# power-v1v35.net
KiCad netlist of a schematic drawn in Altium Designer
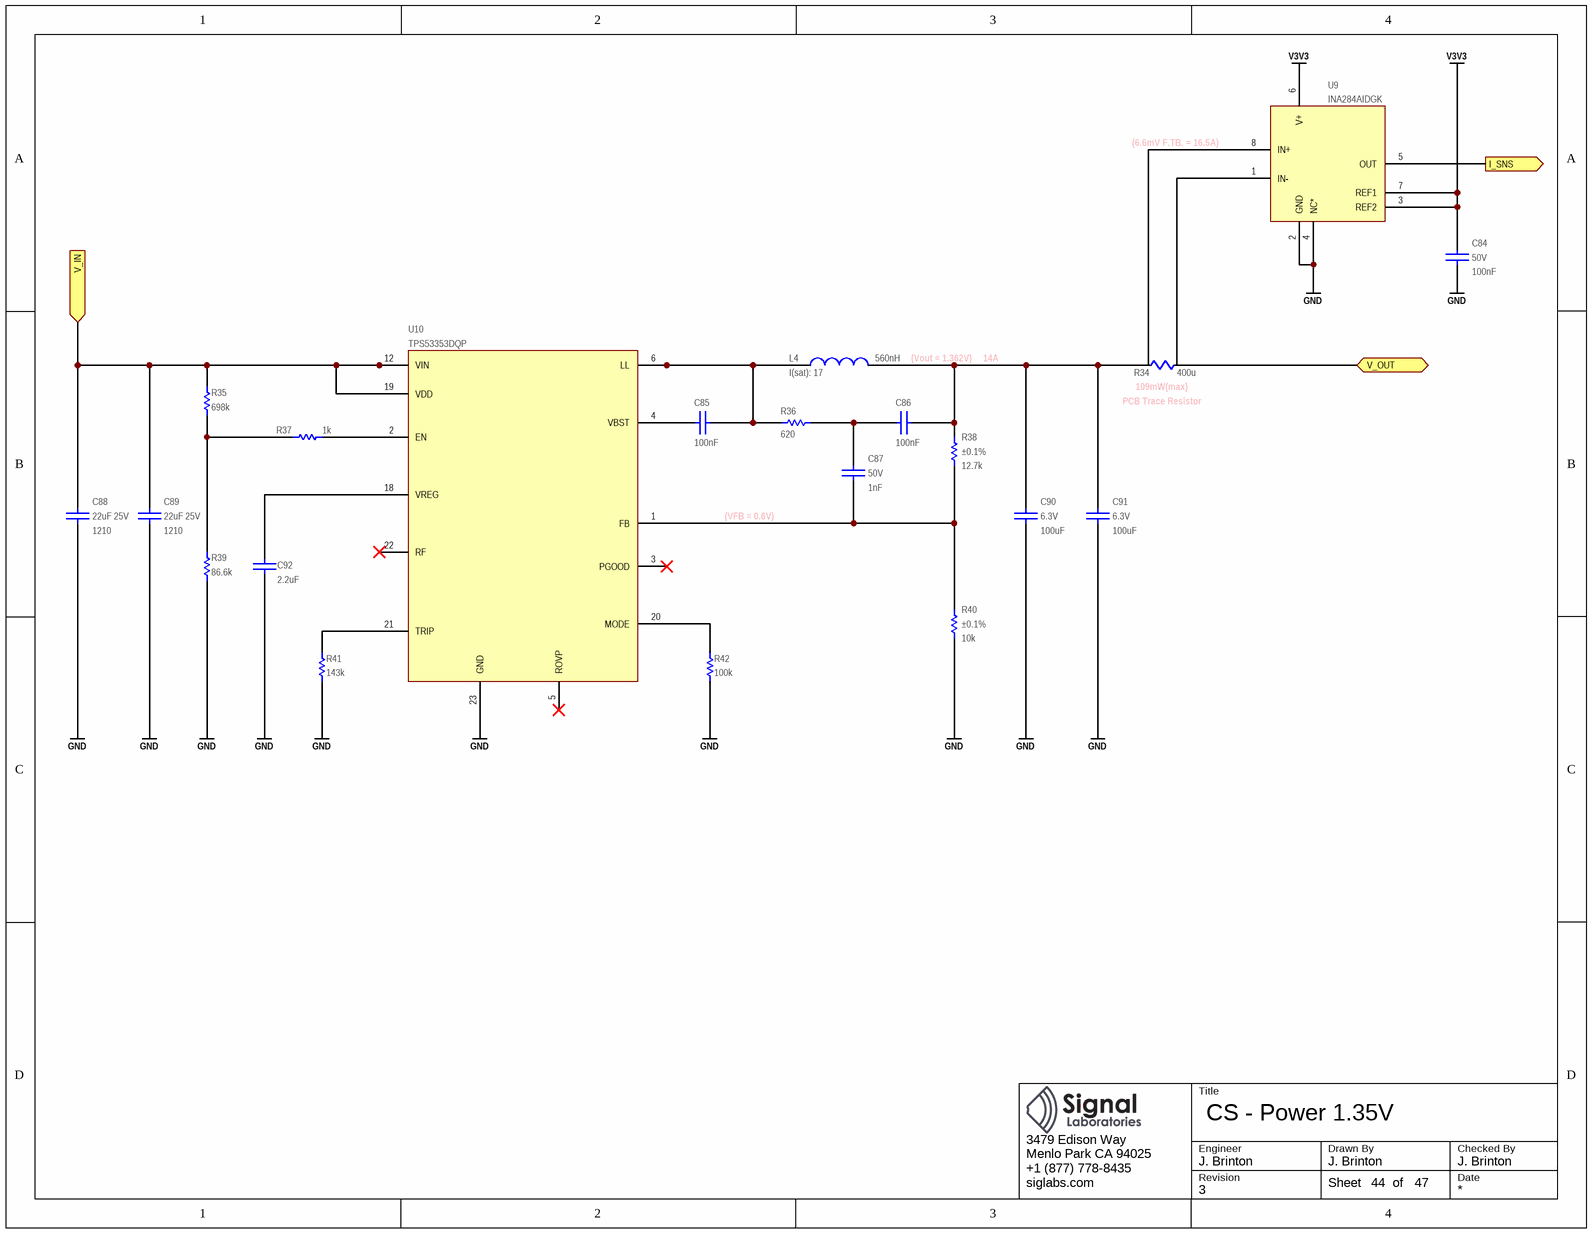
[diagram p0: power-v1v35.SchDoc]

(export (version "E")
  (design (tool "Eeschema 10.0.6"))
  (components
    (comp (ref "C84")
      (value "100nF")
      (footprint "CAPC100X50X55L25N")
      (description "Ceramic Capacitor 100nF ±10% 50V X7R 0402")
      (fields
        (field (name "MANUFACTURER") "Murata")
        (field (name "TOLERANCE") "±10%")
        (field (name "VOLTAGE") "50V")
      )
      (libsource (lib "") (part "CAP_1"))
    )
    (comp (ref "C85")
      (value "100nF")
      (footprint "CAPC100X50X55L25N")
      (description "Ceramic Capacitor 100nF ±10% 50V X7R 0402")
      (fields (field (name "MANUFACTURER") "Murata") (field (name "VOLTAGE") "50V"))
      (libsource (lib "generic") (part "CAP"))
    )
    (comp (ref "C86")
      (value "100nF")
      (footprint "CAPC100X50X55L25N")
      (description "Ceramic Capacitor 100nF ±10% 50V X7R 0402")
      (fields (field (name "MANUFACTURER") "Murata") (field (name "VOLTAGE") "50V"))
      (libsource (lib "generic") (part "CAP"))
    )
    (comp (ref "C87")
      (value "1nF")
      (footprint "CAPC100X50X55L25N")
      (description "Ceramic Capacitor 1nF ±10% 50V X7R 0402")
      (fields
        (field (name "MANUFACTURER") "Murata")
        (field (name "TOLERANCE") "±10%")
        (field (name "VOLTAGE") "50V")
      )
      (libsource (lib "") (part "CAP_1"))
    )
    (comp (ref "C88")
      (value "22uF")
      (footprint "CAPC320X250X270L50N")
      (description "Ceramic Capacitor 22uF ±10% 25V X7R 1210")
      (fields
        (field (name "MANUFACTURER") "Murata")
        (field (name "TOLERANCE") "±10%")
        (field (name "VOLTAGE") "25V")
        (field (name "PACKAGE") "1210")
      )
      (libsource (lib "generic") (part "CAP"))
    )
    (comp (ref "C89")
      (value "22uF")
      (footprint "CAPC320X250X270L50N")
      (description "Ceramic Capacitor 22uF ±10% 25V X7R 1210")
      (fields
        (field (name "MANUFACTURER") "Murata")
        (field (name "TOLERANCE") "±10%")
        (field (name "VOLTAGE") "25V")
        (field (name "PACKAGE") "1210")
      )
      (libsource (lib "generic") (part "CAP"))
    )
    (comp (ref "C90")
      (value "100uF")
      (footprint "CAPC320X250X280L50N")
      (description "Ceramic Capacitor 100uF ±20% 6.3V X6S 1210")
      (fields
        (field (name "MANUFACTURER") "TDK")
        (field (name "TOLERANCE") "±20%")
        (field (name "VOLTAGE") "6.3V")
      )
      (libsource (lib "") (part "CAP_1"))
    )
    (comp (ref "C91")
      (value "100uF")
      (footprint "CAPC320X250X280L50N")
      (description "Ceramic Capacitor 100uF ±20% 6.3V X6S 1210")
      (fields
        (field (name "MANUFACTURER") "TDK")
        (field (name "TOLERANCE") "±20%")
        (field (name "VOLTAGE") "6.3V")
      )
      (libsource (lib "") (part "CAP_1"))
    )
    (comp (ref "C92")
      (value "2.2uF")
      (footprint "CAPC160X80X90L20N")
      (description "Ceramic Capacitor 2.2uF ±20% 10V X7R 0603")
      (fields (field (name "MANUFACTURER") "TDK") (field (name "TOLERANCE") "±20%"))
      (libsource (lib "generic") (part "CAP"))
    )
    (comp (ref "L4")
      (value "560nH")
      (footprint "coilcraft:XAL6030")
      (description "Shielded Power Inductor 560nH, 17A")
      (fields
        (field (name "MANUFACTURER") "Coilcraft")
        (field (name "I(SAT)") "17")
        (field (name "Comment") "XAL6030-561ME")
      )
      (libsource (lib "generic") (part "INDUCTOR"))
    )
    (comp (ref "R34")
      (value "400u")
      (footprint "RES0.0004")
      (description "Current Sense Resistor 400uOhm TRACE")
      (fields (field (name "Comment") "RES0.0004"))
      (libsource (lib "copper_suicide") (part "RES0.0004"))
    )
    (comp (ref "R35")
      (value "698k")
      (footprint "RESC1005X40N")
      (description "Thick Film Resistor 698k ±1% 0.1W 50V 0402")
      (fields (field (name "MANUFACTURER") "Panasonic") (field (name "TOLERANCE") "±1%"))
      (libsource (lib "generic") (part "RES"))
    )
    (comp (ref "R36")
      (value "620")
      (footprint "RESC1005X40N")
      (description "Thick Film Resistor 620 ±1% 0.1W 50V 0402")
      (fields (field (name "MANUFACTURER") "Panasonic") (field (name "TOLERANCE") "±1%"))
      (libsource (lib "generic") (part "RES"))
    )
    (comp (ref "R37")
      (value "1k")
      (footprint "RESC1005X40N")
      (description "Thick Film Resistor 1k ±1% 0.1W 50V 0402")
      (fields (field (name "MANUFACTURER") "Panasonic") (field (name "TOLERANCE") "±1%"))
      (libsource (lib "generic") (part "RES"))
    )
    (comp (ref "R38")
      (value "12.7k")
      (footprint "RESC2012X70N")
      (description "Thin Film Resistor 12.7k ±0.1% 0.125W 100V 0805")
      (fields
        (field (name "TOLERANCE") "±0.1%")
        (field (name "MANUFACTURER") "Panasonic")
        (field (name "VOLTAGE") "100")
      )
      (libsource (lib "generic") (part "RES"))
    )
    (comp (ref "R39")
      (value "86.6k")
      (footprint "RESC1005X40N")
      (description "Thick Film Resistor 86.6k ±1% 0.1W 50V 0402")
      (fields (field (name "MANUFACTURER") "Panasonic") (field (name "TOLERANCE") "±1%"))
      (libsource (lib "generic") (part "RES"))
    )
    (comp (ref "R40")
      (value "10k")
      (footprint "RESC2012X70N")
      (description "Thin Film Resistor 10k ±0.1% 0.125W 100V 0805")
      (fields
        (field (name "TOLERANCE") "±0.1%")
        (field (name "MANUFACTURER") "Panasonic")
        (field (name "VOLTAGE") "100")
      )
      (libsource (lib "generic") (part "RES"))
    )
    (comp (ref "R41")
      (value "143k")
      (footprint "RESC1005X40N")
      (description "Thick Film Resistor 143k ±1% 0.1W 50V 0402")
      (fields (field (name "MANUFACTURER") "Panasonic") (field (name "TOLERANCE") "±1%"))
      (libsource (lib "generic") (part "RES"))
    )
    (comp (ref "R42")
      (value "100k")
      (footprint "RESC1005X40N")
      (description "Thick Film Resistor 100k ±1% 0.1W 50V 0402")
      (fields (field (name "MANUFACTURER") "Panasonic") (field (name "TOLERANCE") "±1%"))
      (libsource (lib "generic") (part "RES"))
    )
    (comp (ref "U9")
      (value "INA284AIDGK")
      (footprint "texas_instruments:S-PDSO-G8")
      (description "Bidirectional Current Shunt Monitor")
      (fields (field (name "MANUFACTURER") "Texas Instruments"))
      (libsource (lib "ti") (part "INA283AIDGK"))
    )
    (comp (ref "U10")
      (value "TPS53353DQP")
      (footprint "texas_instruments:DQP")
      (description "Synchronous Buck Converter 20A")
      (fields
        (field (name "MANUFACTURER") "Texas Instruments")
        (field (name "MANUFACTURER P/N") "TPS53353DQP")
      )
      (libsource (lib "ti") (part "TPS53319DQPR"))
    )
  )
  (nets
    (net (code "1") (name "/I_SNS") (class "Default")
      (node (ref "U9") (pin "5") (pinfunction "OUT_5") (pintype "passive"))
    )
    (net (code "2") (name "/V_IN") (class "Default")
      (node (ref "C88") (pin "2") (pinfunction "2_2") (pintype "passive"))
      (node (ref "C89") (pin "2") (pinfunction "2_2") (pintype "passive"))
      (node (ref "R35") (pin "1") (pinfunction "1_1") (pintype "passive"))
      (node (ref "U10") (pin "12") (pinfunction "VIN_12") (pintype "passive"))
      (node (ref "U10") (pin "13") (pinfunction "VIN_13") (pintype "passive"))
      (node (ref "U10") (pin "14") (pinfunction "VIN_14") (pintype "passive"))
      (node (ref "U10") (pin "15") (pinfunction "VIN_15") (pintype "passive"))
      (node (ref "U10") (pin "16") (pinfunction "VIN_16") (pintype "passive"))
      (node (ref "U10") (pin "17") (pinfunction "VIN_17") (pintype "passive"))
      (node (ref "U10") (pin "19") (pinfunction "VDD_19") (pintype "passive"))
    )
    (net (code "3") (name "/V_OUT") (class "Default") (node (ref "R34") (pin "2") (pintype "passive")))
    (net (code "4") (name "GND") (class "Default")
      (node (ref "C84") (pin "1") (pinfunction "1_1") (pintype "passive"))
      (node (ref "C88") (pin "1") (pinfunction "1_1") (pintype "passive"))
      (node (ref "C89") (pin "1") (pinfunction "1_1") (pintype "passive"))
      (node (ref "C90") (pin "2") (pinfunction "2_2") (pintype "passive"))
      (node (ref "C91") (pin "2") (pinfunction "2_2") (pintype "passive"))
      (node (ref "C92") (pin "1") (pinfunction "1_1") (pintype "passive"))
      (node (ref "R39") (pin "2") (pinfunction "2_2") (pintype "passive"))
      (node (ref "R40") (pin "1") (pinfunction "1_1") (pintype "passive"))
      (node (ref "R41") (pin "2") (pinfunction "2_2") (pintype "passive"))
      (node (ref "R42") (pin "2") (pinfunction "2_2") (pintype "passive"))
      (node (ref "U10") (pin "23") (pinfunction "GND_23") (pintype "passive"))
      (node (ref "U9") (pin "2") (pinfunction "GND_2") (pintype "passive"))
      (node (ref "U9") (pin "4") (pinfunction "NC*_4") (pintype "passive"))
    )
    (net (code "5") (name "Net-(C85-Pad1)") (class "Default")
      (node (ref "C85") (pin "1") (pinfunction "1_1") (pintype "passive"))
      (node (ref "L4") (pin "1") (pinfunction "1_1") (pintype "passive"))
      (node (ref "R36") (pin "2") (pinfunction "2_2") (pintype "passive"))
      (node (ref "U10") (pin "10") (pinfunction "LL_10") (pintype "passive"))
      (node (ref "U10") (pin "11") (pinfunction "LL_11") (pintype "passive"))
      (node (ref "U10") (pin "6") (pinfunction "LL_6") (pintype "passive"))
      (node (ref "U10") (pin "7") (pinfunction "LL_7") (pintype "passive"))
      (node (ref "U10") (pin "8") (pinfunction "LL_8") (pintype "passive"))
      (node (ref "U10") (pin "9") (pinfunction "LL_9") (pintype "passive"))
    )
    (net (code "6") (name "Net-(C86-Pad1)") (class "Default")
      (node (ref "C86") (pin "1") (pinfunction "1_1") (pintype "passive"))
      (node (ref "C90") (pin "1") (pinfunction "1_1") (pintype "passive"))
      (node (ref "C91") (pin "1") (pinfunction "1_1") (pintype "passive"))
      (node (ref "L4") (pin "2") (pinfunction "2_2") (pintype "passive"))
      (node (ref "R34") (pin "1") (pintype "passive"))
      (node (ref "R38") (pin "2") (pinfunction "2_2") (pintype "passive"))
    )
    (net (code "7") (name "Net-(C86-Pad2)") (class "Default")
      (node (ref "C86") (pin "2") (pinfunction "2_2") (pintype "passive"))
      (node (ref "C87") (pin "1") (pinfunction "1_1") (pintype "passive"))
      (node (ref "R36") (pin "1") (pinfunction "1_1") (pintype "passive"))
    )
    (net (code "8") (name "Net-(R35-Pad2)") (class "Default")
      (node (ref "R35") (pin "2") (pinfunction "2_2") (pintype "passive"))
      (node (ref "R37") (pin "1") (pinfunction "1_1") (pintype "passive"))
      (node (ref "R39") (pin "1") (pinfunction "1_1") (pintype "passive"))
    )
    (net (code "9") (name "Net-(U9-IN+)") (class "Default")
      (node (ref "R34") (pin "3") (pintype "passive"))
      (node (ref "U9") (pin "8") (pinfunction "IN+_8") (pintype "passive"))
    )
    (net (code "10") (name "Net-(U9-IN-)") (class "Default")
      (node (ref "R34") (pin "4") (pintype "passive"))
      (node (ref "U9") (pin "1") (pinfunction "IN-_1") (pintype "passive"))
    )
    (net (code "11") (name "Net-(U10-EN)") (class "Default")
      (node (ref "R37") (pin "2") (pinfunction "2_2") (pintype "passive"))
      (node (ref "U10") (pin "2") (pinfunction "EN_2") (pintype "passive"))
    )
    (net (code "12") (name "Net-(U10-FB)") (class "Default")
      (node (ref "C87") (pin "2") (pinfunction "2_2") (pintype "passive"))
      (node (ref "R38") (pin "1") (pinfunction "1_1") (pintype "passive"))
      (node (ref "R40") (pin "2") (pinfunction "2_2") (pintype "passive"))
      (node (ref "U10") (pin "1") (pinfunction "FB_1") (pintype "passive"))
    )
    (net (code "13") (name "Net-(U10-MODE)") (class "Default")
      (node (ref "R42") (pin "1") (pinfunction "1_1") (pintype "passive"))
      (node (ref "U10") (pin "20") (pinfunction "MODE_20") (pintype "passive"))
    )
    (net (code "14") (name "Net-(U10-TRIP)") (class "Default")
      (node (ref "R41") (pin "1") (pinfunction "1_1") (pintype "passive"))
      (node (ref "U10") (pin "21") (pinfunction "TRIP_21") (pintype "passive"))
    )
    (net (code "15") (name "Net-(U10-VBST)") (class "Default")
      (node (ref "C85") (pin "2") (pinfunction "2_2") (pintype "passive"))
      (node (ref "U10") (pin "4") (pinfunction "VBST_4") (pintype "passive"))
    )
    (net (code "16") (name "Net-(U10-VREG)") (class "Default")
      (node (ref "C92") (pin "2") (pinfunction "2_2") (pintype "passive"))
      (node (ref "U10") (pin "18") (pinfunction "VREG_18") (pintype "passive"))
    )
    (net (code "17") (name "V3V3") (class "Default")
      (node (ref "C84") (pin "2") (pinfunction "2_2") (pintype "passive"))
      (node (ref "U9") (pin "3") (pinfunction "REF2_3") (pintype "passive"))
      (node (ref "U9") (pin "6") (pinfunction "V+_6") (pintype "passive"))
      (node (ref "U9") (pin "7") (pinfunction "REF1_7") (pintype "passive"))
    )
    (net (code "18") (name "unconnected-(U10-PGOOD-Pad3)") (class "Default")
      (node (ref "U10") (pin "3") (pinfunction "PGOOD_3") (pintype "passive+no_connect"))
    )
    (net (code "19") (name "unconnected-(U10-RF-Pad22)") (class "Default")
      (node (ref "U10") (pin "22") (pinfunction "RF_22") (pintype "passive+no_connect"))
    )
    (net (code "20") (name "unconnected-(U10-ROVP-Pad5)") (class "Default")
      (node (ref "U10") (pin "5") (pinfunction "ROVP_5") (pintype "passive+no_connect"))
    )
  )
)
